# MODELO_TRANSFORMADOR.net
KiCad netlist of a schematic drawn in Altium Designer
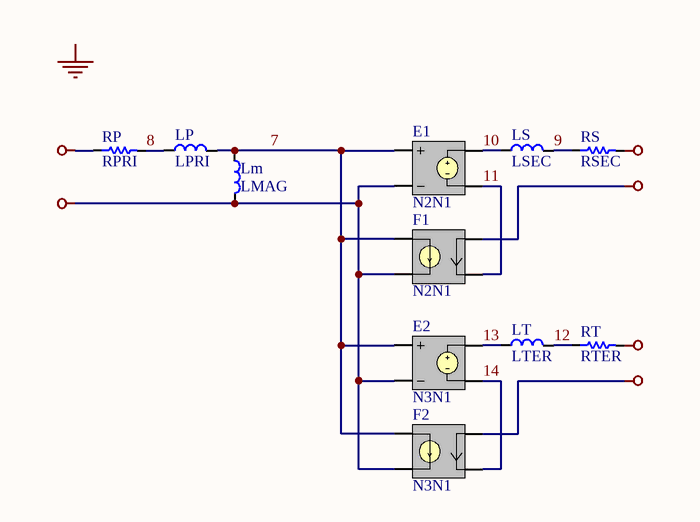
[diagram p0: MODELO TRANSFORMADOR.SCHDOC]

(export (version "E")
  (design (tool "Eeschema 10.0.6"))
  (components
    (comp (ref "E1")
      (value "ESRC")
      (description "Voltage Controlled Voltage Source")
      (fields (field (name "GAIN") "N2N1") (field (name "PUBLISHER") "Altium Limited"))
      (libsource (lib "Simulation Sources") (part "ESRC"))
    )
    (comp (ref "E2")
      (value "ESRC")
      (description "Voltage Controlled Voltage Source")
      (fields (field (name "GAIN") "N3N1") (field (name "PUBLISHER") "Altium Limited"))
      (libsource (lib "Simulation Sources") (part "ESRC"))
    )
    (comp (ref "F1")
      (value "FSRC")
      (description "Current Controlled Current Source")
      (fields (field (name "GAIN") "N2N1") (field (name "PUBLISHER") "Altium Limited"))
      (libsource (lib "Simulation Sources") (part "FSRC"))
    )
    (comp (ref "F2")
      (value "FSRC")
      (description "Current Controlled Current Source")
      (fields (field (name "GAIN") "N3N1") (field (name "PUBLISHER") "Altium Limited"))
      (libsource (lib "Simulation Sources") (part "FSRC"))
    )
    (comp (ref "Lm")
      (value "LMAG")
      (footprint "TOROIDE TN14-9-5")
      (description "Inductor")
      (fields (field (name "Comment") "Inductor2"))
      (libsource (lib "FEDE") (part "Inductor2"))
    )
    (comp (ref "LP")
      (value "LPRI")
      (footprint "TOROIDE TN14-9-5")
      (description "Inductor")
      (fields (field (name "Comment") "Inductor2"))
      (libsource (lib "FEDE") (part "Inductor2"))
    )
    (comp (ref "LS")
      (value "LSEC")
      (footprint "TOROIDE TN14-9-5")
      (description "Inductor")
      (fields (field (name "Comment") "Inductor2"))
      (libsource (lib "FEDE") (part "Inductor2"))
    )
    (comp (ref "LT")
      (value "LTER")
      (footprint "TOROIDE TN14-9-5")
      (description "Inductor")
      (fields (field (name "Comment") "Inductor2"))
      (libsource (lib "FEDE") (part "Inductor2"))
    )
    (comp (ref "RP")
      (value "RPRI")
      (footprint "0805")
      (description "Resistor")
      (fields (field (name "POWER") "0.25W") (field (name "Comment") "Res"))
      (libsource (lib "FEDE") (part "Res"))
    )
    (comp (ref "RS")
      (value "RSEC")
      (footprint "0805")
      (description "Resistor")
      (fields (field (name "POWER") "0.25W") (field (name "Comment") "Res"))
      (libsource (lib "FEDE") (part "Res"))
    )
    (comp (ref "RT")
      (value "RTER")
      (footprint "0805")
      (description "Resistor")
      (fields (field (name "POWER") "0.25W") (field (name "Comment") "Res"))
      (libsource (lib "FEDE") (part "Res"))
    )
  )
  (nets
    (net (code "1") (name "/7") (class "Default")
      (node (ref "E1") (pin "1") (pinfunction "NC+_1") (pintype "passive"))
      (node (ref "E2") (pin "1") (pinfunction "NC+_1") (pintype "passive"))
      (node (ref "F1") (pin "3") (pinfunction "N+_3") (pintype "passive"))
      (node (ref "F2") (pin "3") (pinfunction "N+_3") (pintype "passive"))
      (node (ref "LP") (pin "2") (pinfunction "2_2") (pintype "passive"))
      (node (ref "Lm") (pin "1") (pinfunction "1_1") (pintype "passive"))
    )
    (net (code "2") (name "/8") (class "Default")
      (node (ref "LP") (pin "1") (pinfunction "1_1") (pintype "passive"))
      (node (ref "RP") (pin "2") (pinfunction "2_2") (pintype "passive"))
    )
    (net (code "3") (name "/9") (class "Default")
      (node (ref "LS") (pin "2") (pinfunction "2_2") (pintype "passive"))
      (node (ref "RS") (pin "1") (pinfunction "1_1") (pintype "passive"))
    )
    (net (code "4") (name "/10") (class "Default")
      (node (ref "E1") (pin "3") (pinfunction "N+_3") (pintype "passive"))
      (node (ref "LS") (pin "1") (pinfunction "1_1") (pintype "passive"))
    )
    (net (code "5") (name "/11") (class "Default")
      (node (ref "E1") (pin "4") (pinfunction "N-_4") (pintype "passive"))
      (node (ref "F1") (pin "2") (pinfunction "NC-_2") (pintype "passive"))
    )
    (net (code "6") (name "/12") (class "Default")
      (node (ref "LT") (pin "2") (pinfunction "2_2") (pintype "passive"))
      (node (ref "RT") (pin "1") (pinfunction "1_1") (pintype "passive"))
    )
    (net (code "7") (name "/13") (class "Default")
      (node (ref "E2") (pin "3") (pinfunction "N+_3") (pintype "passive"))
      (node (ref "LT") (pin "1") (pinfunction "1_1") (pintype "passive"))
    )
    (net (code "8") (name "/14") (class "Default")
      (node (ref "E2") (pin "4") (pinfunction "N-_4") (pintype "passive"))
      (node (ref "F2") (pin "2") (pinfunction "NC-_2") (pintype "passive"))
    )
    (net (code "9") (name "1") (class "Default")
      (node (ref "RP") (pin "1") (pinfunction "1_1") (pintype "passive"))
    )
    (net (code "10") (name "2") (class "Default")
      (node (ref "E1") (pin "2") (pinfunction "NC-_2") (pintype "passive"))
      (node (ref "E2") (pin "2") (pinfunction "NC-_2") (pintype "passive"))
      (node (ref "F1") (pin "4") (pinfunction "N-_4") (pintype "passive"))
      (node (ref "F2") (pin "4") (pinfunction "N-_4") (pintype "passive"))
      (node (ref "Lm") (pin "2") (pinfunction "2_2") (pintype "passive"))
    )
    (net (code "11") (name "3") (class "Default")
      (node (ref "RS") (pin "2") (pinfunction "2_2") (pintype "passive"))
    )
    (net (code "12") (name "4") (class "Default")
      (node (ref "F1") (pin "1") (pinfunction "NC+_1") (pintype "passive"))
    )
    (net (code "13") (name "5") (class "Default")
      (node (ref "RT") (pin "2") (pinfunction "2_2") (pintype "passive"))
    )
    (net (code "14") (name "6") (class "Default")
      (node (ref "F2") (pin "1") (pinfunction "NC+_1") (pintype "passive"))
    )
  )
)
